# Transitorio.net
KiCad netlist of a schematic drawn in Altium Designer
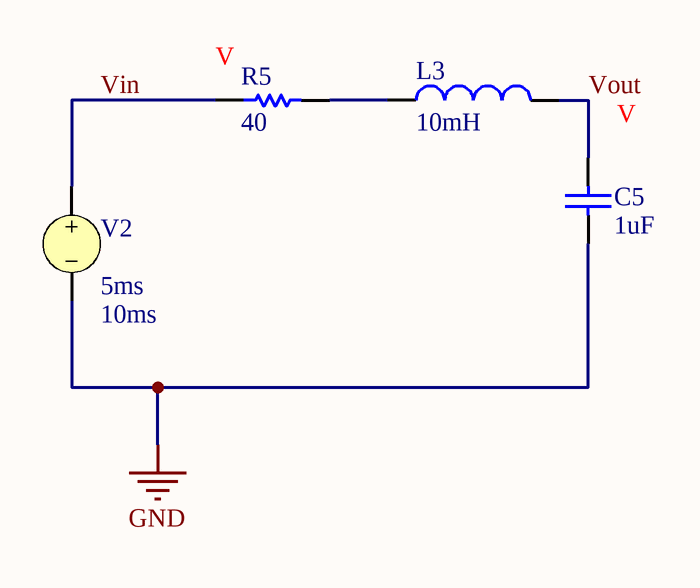
[diagram p0: Transitorio.SchDoc]

(export (version "E")
  (design (tool "Eeschema 10.0.6"))
  (components
    (comp (ref "C5")
      (value "1uF")
      (description "Capacitor")
      (libsource (lib "Simulation Generic Components") (part "Capacitor"))
    )
    (comp (ref "L3")
      (value "10mH")
      (description "Inductor")
      (libsource (lib "Simulation Generic Components") (part "Inductor"))
    )
    (comp (ref "R5")
      (value "40")
      (description "Resistor")
      (libsource (lib "Simulation Generic Components") (part "Resistor"))
    )
    (comp (ref "V2")
      (value "PULSE(0 1 100n 10n 10n 5ms 10ms 0)")
      (description "Voltage Source")
      (fields
        (field (name "PULSE WIDTH") "5ms")
        (field (name "PERIOD") "10ms")
        (field (name "PUBLISHER") "Altium Limited")
      )
      (libsource (lib "Simulation Generic Components") (part "VSRC"))
    )
  )
  (nets
    (net (code "1") (name "/Vin") (class "Default")
      (node (ref "R5") (pin "1") (pinfunction "1_1") (pintype "passive"))
      (node (ref "V2") (pin "1") (pinfunction "1_1") (pintype "passive"))
    )
    (net (code "2") (name "/Vout") (class "Default")
      (node (ref "C5") (pin "2") (pinfunction "2_2") (pintype "passive"))
      (node (ref "L3") (pin "2") (pinfunction "2_2") (pintype "passive"))
    )
    (net (code "3") (name "GND") (class "Default")
      (node (ref "C5") (pin "1") (pinfunction "1_1") (pintype "passive"))
      (node (ref "V2") (pin "2") (pinfunction "2_2") (pintype "passive"))
    )
    (net (code "4") (name "Net-(L3-Pad1)") (class "Default")
      (node (ref "L3") (pin "1") (pinfunction "1_1") (pintype "passive"))
      (node (ref "R5") (pin "2") (pinfunction "2_2") (pintype "passive"))
    )
  )
)
